# BATT_CONNECTOR.net
KiCad netlist of a schematic drawn in EAGLE
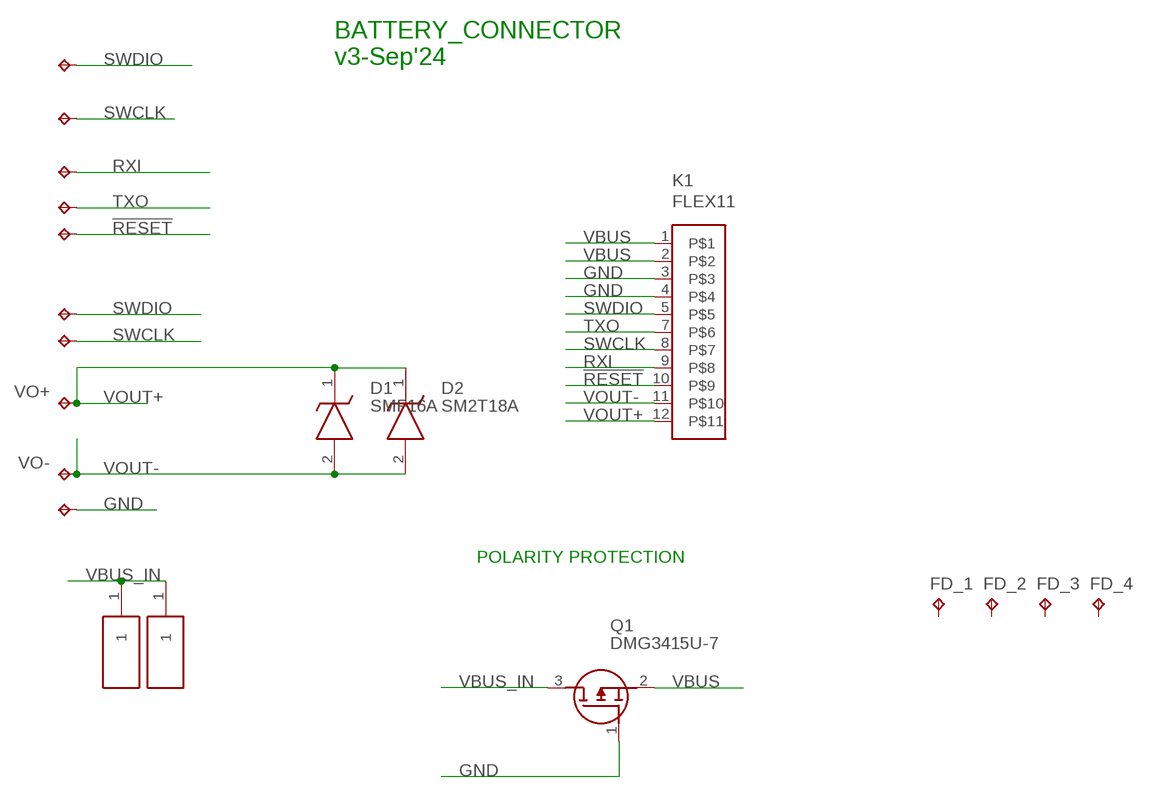
[diagram p0: schematic, sheet 1]

(export (version "E")
  (design (tool "Eeschema 10.0.6"))
  (components
    (comp (ref "!RESET")
      (value "TPB2,54")
      (footprint "eagle-import:B2,54")
      (libsource (lib "eagle-import") (part "TPB2,54"))
    )
    (comp (ref "D1")
      (value "SMF16A")
      (footprint "eagle-import:SODFL3618X110N")
      (fields (field (name "MOUSER_PART_NUMBER") "576-SMF16A"))
      (libsource (lib "eagle-import") (part "SMF16A"))
    )
    (comp (ref "D2")
      (value "SM2T18A")
      (footprint "eagle-import:SM2T18A")
      (fields (field (name "MOUSER_PART_NUMBER") "511-SM2T18A"))
      (libsource (lib "eagle-import") (part "SM2T18A"))
    )
    (comp (ref "DAT")
      (value "TPB2,54")
      (footprint "eagle-import:B2,54")
      (libsource (lib "eagle-import") (part "TPB2,54"))
    )
    (comp (ref "FD_1")
      (value "FD_1")
      (footprint "eagle-import:TP06SQ")
      (libsource (lib "eagle-import") (part "TPTP06SQ"))
    )
    (comp (ref "FD_2")
      (value "FD_1")
      (footprint "eagle-import:TP06SQ")
      (libsource (lib "eagle-import") (part "TPTP06SQ"))
    )
    (comp (ref "FD_3")
      (value "FD_1")
      (footprint "eagle-import:TP06SQ")
      (libsource (lib "eagle-import") (part "TPTP06SQ"))
    )
    (comp (ref "FD_4")
      (value "FD_1")
      (footprint "eagle-import:TP06SQ")
      (libsource (lib "eagle-import") (part "TPTP06SQ"))
    )
    (comp (ref "GND")
      (value "TPB2,54")
      (footprint "eagle-import:B2,54")
      (libsource (lib "eagle-import") (part "TPB2,54"))
    )
    (comp (ref "H1")
      (value "S1761-42R")
      (footprint "eagle-import:S176142R")
      (fields (field (name "MOUSER_PART_NUMBER") "855-S1761-42R"))
      (libsource (lib "eagle-import") (part "S1761-42R"))
    )
    (comp (ref "H2")
      (value "S1761-42R")
      (footprint "eagle-import:S176142R")
      (fields (field (name "MOUSER_PART_NUMBER") "855-S1761-42R"))
      (libsource (lib "eagle-import") (part "S1761-42R"))
    )
    (comp (ref "ID")
      (value "TPB2,54")
      (footprint "eagle-import:B2,54")
      (libsource (lib "eagle-import") (part "TPB2,54"))
    )
    (comp (ref "K1")
      (value "FLEX11")
      (footprint "eagle-import:FLEX11")
      (libsource (lib "eagle-import") (part "FLEX11"))
    )
    (comp (ref "Q1")
      (value "DMG3415U-7")
      (footprint "eagle-import:SSM3J332RLFT")
      (fields
        (field (name "ARROW_PART_NUMBER") "SSM3J338R,LF")
        (field (name "MOUSER_PART_NUMBER") "757-SSM3J338RLF")
      )
      (libsource (lib "eagle-import") (part "SSM3J338R,LF"))
    )
    (comp (ref "RXI")
      (value "TPB2,54")
      (footprint "eagle-import:B2,54")
      (libsource (lib "eagle-import") (part "TPB2,54"))
    )
    (comp (ref "SWCLK")
      (value "TPB2,54")
      (footprint "eagle-import:B2,54")
      (libsource (lib "eagle-import") (part "TPB2,54"))
    )
    (comp (ref "SWDIO")
      (value "TPB2,54")
      (footprint "eagle-import:B2,54")
      (libsource (lib "eagle-import") (part "TPB2,54"))
    )
    (comp (ref "TXO")
      (value "TPB2,54")
      (footprint "eagle-import:B2,54")
      (libsource (lib "eagle-import") (part "TPB2,54"))
    )
    (comp (ref "VO+")
      (value "TPB2,54")
      (footprint "eagle-import:B2,54")
      (libsource (lib "eagle-import") (part "TPB2,54"))
    )
    (comp (ref "VO-")
      (value "TPB2,54")
      (footprint "eagle-import:B2,54")
      (libsource (lib "eagle-import") (part "TPB2,54"))
    )
  )
  (nets
    (net (code "1") (name "/GND") (class "Default")
      (node (ref "GND") (pin "TP") (pinfunction "TP_TP") (pintype "input"))
      (node (ref "K1") (pin "3") (pinfunction "P$3_3") (pintype "bidirectional"))
      (node (ref "K1") (pin "4") (pinfunction "P$4_4") (pintype "bidirectional"))
      (node (ref "Q1") (pin "1") (pinfunction "G_1") (pintype "bidirectional"))
    )
    (net (code "2") (name "/RXI") (class "Default")
      (node (ref "K1") (pin "9") (pinfunction "P$8_9") (pintype "bidirectional"))
      (node (ref "RXI") (pin "TP") (pinfunction "TP_TP") (pintype "input"))
    )
    (net (code "3") (name "/SWCLK") (class "Default")
      (node (ref "ID") (pin "TP") (pinfunction "TP_TP") (pintype "input"))
      (node (ref "K1") (pin "8") (pinfunction "P$7_8") (pintype "bidirectional"))
      (node (ref "SWCLK") (pin "TP") (pinfunction "TP_TP") (pintype "input"))
    )
    (net (code "4") (name "/SWDIO") (class "Default")
      (node (ref "DAT") (pin "TP") (pinfunction "TP_TP") (pintype "input"))
      (node (ref "K1") (pin "5") (pinfunction "P$5_5") (pintype "bidirectional"))
      (node (ref "SWDIO") (pin "TP") (pinfunction "TP_TP") (pintype "input"))
    )
    (net (code "5") (name "/TXO") (class "Default")
      (node (ref "K1") (pin "7") (pinfunction "P$6_7") (pintype "bidirectional"))
      (node (ref "TXO") (pin "TP") (pinfunction "TP_TP") (pintype "input"))
    )
    (net (code "6") (name "/VBUS") (class "Default")
      (node (ref "K1") (pin "1") (pinfunction "P$1_1") (pintype "bidirectional"))
      (node (ref "K1") (pin "2") (pinfunction "P$2_2") (pintype "bidirectional"))
      (node (ref "Q1") (pin "2") (pinfunction "S_2") (pintype "bidirectional"))
    )
    (net (code "7") (name "/VBUS_IN") (class "Default")
      (node (ref "H1") (pin "1") (pinfunction "1_1") (pintype "bidirectional"))
      (node (ref "H2") (pin "1") (pinfunction "1_1") (pintype "bidirectional"))
      (node (ref "Q1") (pin "3") (pinfunction "D_3") (pintype "bidirectional"))
    )
    (net (code "8") (name "/VOUT+") (class "Default")
      (node (ref "D1") (pin "1") (pinfunction "K_1") (pintype "bidirectional"))
      (node (ref "D2") (pin "1") (pinfunction "K_1") (pintype "bidirectional"))
      (node (ref "K1") (pin "12") (pinfunction "P$11_12") (pintype "bidirectional"))
      (node (ref "VO+") (pin "TP") (pinfunction "TP_TP") (pintype "input"))
    )
    (net (code "9") (name "/VOUT-") (class "Default")
      (node (ref "D1") (pin "2") (pinfunction "A_2") (pintype "bidirectional"))
      (node (ref "D2") (pin "2") (pinfunction "A_2") (pintype "bidirectional"))
      (node (ref "K1") (pin "11") (pinfunction "P$10_11") (pintype "bidirectional"))
      (node (ref "VO-") (pin "TP") (pinfunction "TP_TP") (pintype "input"))
    )
    (net (code "10") (name "/~{RESET}") (class "Default")
      (node (ref "!RESET") (pin "TP") (pinfunction "TP_TP") (pintype "input"))
      (node (ref "K1") (pin "10") (pinfunction "P$9_10") (pintype "bidirectional"))
    )
    (net (code "11") (name "unconnected-(FD_1-PadTP)") (class "Default")
      (node (ref "FD_1") (pin "TP") (pinfunction "TP_TP") (pintype "input"))
    )
    (net (code "12") (name "unconnected-(FD_2-PadTP)") (class "Default")
      (node (ref "FD_2") (pin "TP") (pinfunction "TP_TP") (pintype "input"))
    )
    (net (code "13") (name "unconnected-(FD_3-PadTP)") (class "Default")
      (node (ref "FD_3") (pin "TP") (pinfunction "TP_TP") (pintype "input"))
    )
    (net (code "14") (name "unconnected-(FD_4-PadTP)") (class "Default")
      (node (ref "FD_4") (pin "TP") (pinfunction "TP_TP") (pintype "input"))
    )
  )
)
